# Pedalboard.net
KiCad netlist of a schematic drawn in EAGLE
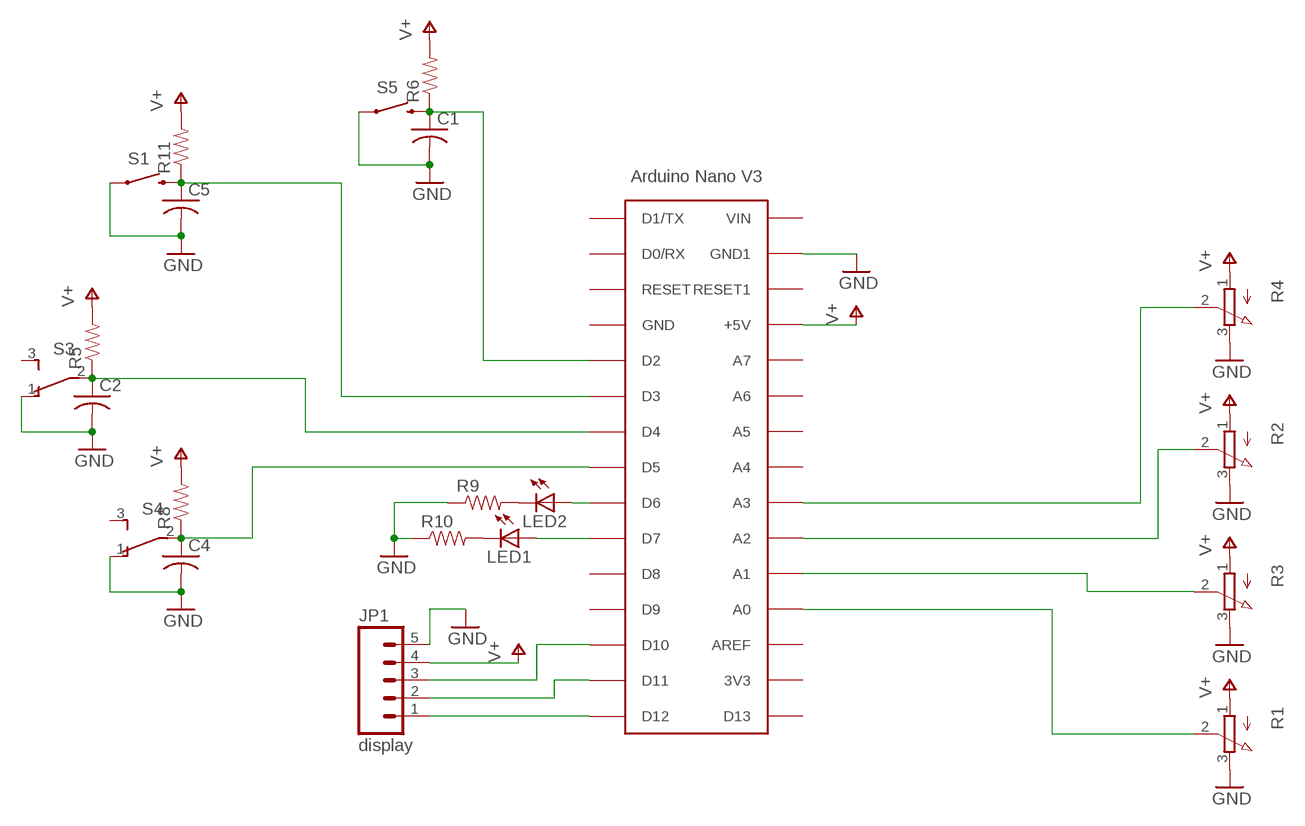
[diagram p0: schematic, sheet 1]

(export (version "E")
  (design (tool "Eeschema 10.0.6"))
  (components
    (comp (ref "C1")
      (value "C-US025-025X050")
      (footprint "eagle-import:C025-025X050")
      (libsource (lib "eagle-import") (part "C-US025-025X050"))
    )
    (comp (ref "C2")
      (value "C-US025-025X050")
      (footprint "eagle-import:C025-025X050")
      (libsource (lib "eagle-import") (part "C-US025-025X050"))
    )
    (comp (ref "C4")
      (value "C-US025-025X050")
      (footprint "eagle-import:C025-025X050")
      (libsource (lib "eagle-import") (part "C-US025-025X050"))
    )
    (comp (ref "C5")
      (value "C-US025-025X050")
      (footprint "eagle-import:C025-025X050")
      (libsource (lib "eagle-import") (part "C-US025-025X050"))
    )
    (comp (ref "JP1")
      (value "display")
      (footprint "eagle-import:1X05")
      (libsource (lib "eagle-import") (part "M05PTH"))
    )
    (comp (ref "LED1")
      (value "LED3MM")
      (footprint "eagle-import:LED3MM")
      (libsource (lib "eagle-import") (part "LED3MM"))
    )
    (comp (ref "LED2")
      (value "LED3MM")
      (footprint "eagle-import:LED3MM")
      (libsource (lib "eagle-import") (part "LED3MM"))
    )
    (comp (ref "R1")
      (value "3RP/1610N")
      (footprint "eagle-import:3RP_1610N")
      (libsource (lib "eagle-import") (part "3RP/1610N"))
    )
    (comp (ref "R2")
      (value "3RP/1610N")
      (footprint "eagle-import:3RP_1610N")
      (libsource (lib "eagle-import") (part "3RP/1610N"))
    )
    (comp (ref "R3")
      (value "3RP/1610N")
      (footprint "eagle-import:3RP_1610N")
      (libsource (lib "eagle-import") (part "3RP/1610N"))
    )
    (comp (ref "R4")
      (value "3RP/1610N")
      (footprint "eagle-import:3RP_1610N")
      (libsource (lib "eagle-import") (part "3RP/1610N"))
    )
    (comp (ref "R5")
      (value "RESISTOREZ")
      (footprint "eagle-import:AXIAL-0.3EZ")
      (libsource (lib "eagle-import") (part "RESISTOREZ"))
    )
    (comp (ref "R6")
      (value "RESISTOREZ")
      (footprint "eagle-import:AXIAL-0.3EZ")
      (libsource (lib "eagle-import") (part "RESISTOREZ"))
    )
    (comp (ref "R8")
      (value "RESISTOREZ")
      (footprint "eagle-import:AXIAL-0.3EZ")
      (libsource (lib "eagle-import") (part "RESISTOREZ"))
    )
    (comp (ref "R9")
      (value "RESISTOREZ")
      (footprint "eagle-import:AXIAL-0.3EZ")
      (libsource (lib "eagle-import") (part "RESISTOREZ"))
    )
    (comp (ref "R10")
      (value "RESISTOREZ")
      (footprint "eagle-import:AXIAL-0.3EZ")
      (libsource (lib "eagle-import") (part "RESISTOREZ"))
    )
    (comp (ref "R11")
      (value "RESISTOREZ")
      (footprint "eagle-import:AXIAL-0.3EZ")
      (libsource (lib "eagle-import") (part "RESISTOREZ"))
    )
    (comp (ref "S1")
      (value "SWITCH-MOMENTARY-2TACTILE-SWITCH-SMD-RIGHT-ANGLE")
      (footprint "eagle-import:TACTILE_SWITCH-SMD-RIGHT-ANGLE")
      (libsource (lib "eagle-import") (part "SWITCH-MOMENTARY-2TACTILE-SWITCH-SMD-RIGHT-ANGLE"))
    )
    (comp (ref "S3")
      (value "TL36PO")
      (footprint "eagle-import:TL3XPO")
      (libsource (lib "eagle-import") (part "TL36PO"))
    )
    (comp (ref "S4")
      (value "TL36PO")
      (footprint "eagle-import:TL3XPO")
      (libsource (lib "eagle-import") (part "TL36PO"))
    )
    (comp (ref "S5")
      (value "SWITCH-MOMENTARY-2TACTILE-SWITCH-SMD-RIGHT-ANGLE")
      (footprint "eagle-import:TACTILE_SWITCH-SMD-RIGHT-ANGLE")
      (libsource (lib "eagle-import") (part "SWITCH-MOMENTARY-2TACTILE-SWITCH-SMD-RIGHT-ANGLE"))
    )
    (comp (ref "U$1")
      (value "ARDUINONANO")
      (footprint "eagle-import:PDIP-32")
      (libsource (lib "eagle-import") (part "ARDUINONANO"))
    )
  )
  (nets
    (net (code "1") (name "GND") (class "Default")
      (node (ref "C1") (pin "2") (pinfunction "2_2") (pintype "passive"))
      (node (ref "C2") (pin "2") (pinfunction "2_2") (pintype "passive"))
      (node (ref "C4") (pin "2") (pinfunction "2_2") (pintype "passive"))
      (node (ref "C5") (pin "2") (pinfunction "2_2") (pintype "passive"))
      (node (ref "JP1") (pin "5") (pinfunction "5_5") (pintype "passive"))
      (node (ref "R1") (pin "3") (pinfunction "E_3") (pintype "passive"))
      (node (ref "R10") (pin "P$1") (pinfunction "1_P$1") (pintype "passive"))
      (node (ref "R2") (pin "3") (pinfunction "E_3") (pintype "passive"))
      (node (ref "R3") (pin "3") (pinfunction "E_3") (pintype "passive"))
      (node (ref "R4") (pin "3") (pinfunction "E_3") (pintype "passive"))
      (node (ref "R9") (pin "P$1") (pinfunction "1_P$1") (pintype "passive"))
      (node (ref "S1") (pin "1") (pinfunction "1_1") (pintype "passive"))
      (node (ref "S3") (pin "1") (pinfunction "O_1") (pintype "passive"))
      (node (ref "S4") (pin "1") (pinfunction "O_1") (pintype "passive"))
      (node (ref "S5") (pin "1") (pinfunction "1_1") (pintype "passive"))
      (node (ref "U$1") (pin "GND1") (pinfunction "GND1_GND1") (pintype "bidirectional"))
    )
    (net (code "2") (name "Net-(JP1-Pad1)") (class "Default")
      (node (ref "JP1") (pin "1") (pinfunction "1_1") (pintype "passive"))
      (node (ref "U$1") (pin "D12") (pinfunction "D12_D12") (pintype "bidirectional"))
    )
    (net (code "3") (name "Net-(JP1-Pad2)") (class "Default")
      (node (ref "JP1") (pin "2") (pinfunction "2_2") (pintype "passive"))
      (node (ref "U$1") (pin "D11") (pinfunction "D11_D11") (pintype "bidirectional"))
    )
    (net (code "4") (name "Net-(JP1-Pad3)") (class "Default")
      (node (ref "JP1") (pin "3") (pinfunction "3_3") (pintype "passive"))
      (node (ref "U$1") (pin "D10") (pinfunction "D10_D10") (pintype "bidirectional"))
    )
    (net (code "5") (name "Net-(LED1-C)") (class "Default")
      (node (ref "LED1") (pin "K") (pinfunction "C_K") (pintype "passive"))
      (node (ref "R10") (pin "P$2") (pinfunction "2_P$2") (pintype "passive"))
    )
    (net (code "6") (name "Net-(LED1-PadA)") (class "Default")
      (node (ref "LED1") (pin "A") (pinfunction "A_A") (pintype "passive"))
      (node (ref "U$1") (pin "D7") (pinfunction "D7_D7") (pintype "bidirectional"))
    )
    (net (code "7") (name "Net-(LED2-C)") (class "Default")
      (node (ref "LED2") (pin "K") (pinfunction "C_K") (pintype "passive"))
      (node (ref "R9") (pin "P$2") (pinfunction "2_P$2") (pintype "passive"))
    )
    (net (code "8") (name "Net-(LED2-PadA)") (class "Default")
      (node (ref "LED2") (pin "A") (pinfunction "A_A") (pintype "passive"))
      (node (ref "U$1") (pin "D6") (pinfunction "D6_D6") (pintype "bidirectional"))
    )
    (net (code "9") (name "Net-(R1-S)") (class "Default")
      (node (ref "R1") (pin "2") (pinfunction "S_2") (pintype "passive"))
      (node (ref "U$1") (pin "A7") (pinfunction "A0_A7") (pintype "bidirectional"))
    )
    (net (code "10") (name "Net-(R2-S)") (class "Default")
      (node (ref "R2") (pin "2") (pinfunction "S_2") (pintype "passive"))
      (node (ref "U$1") (pin "A5") (pinfunction "A2_A5") (pintype "bidirectional"))
    )
    (net (code "11") (name "Net-(R3-S)") (class "Default")
      (node (ref "R3") (pin "2") (pinfunction "S_2") (pintype "passive"))
      (node (ref "U$1") (pin "A6") (pinfunction "A1_A6") (pintype "bidirectional"))
    )
    (net (code "12") (name "Net-(R4-S)") (class "Default")
      (node (ref "R4") (pin "2") (pinfunction "S_2") (pintype "passive"))
      (node (ref "U$1") (pin "A4") (pinfunction "A3_A4") (pintype "bidirectional"))
    )
    (net (code "13") (name "Net-(R5-1)") (class "Default")
      (node (ref "C2") (pin "1") (pinfunction "1_1") (pintype "passive"))
      (node (ref "R5") (pin "P$1") (pinfunction "1_P$1") (pintype "passive"))
      (node (ref "S3") (pin "2") (pinfunction "P_2") (pintype "passive"))
      (node (ref "U$1") (pin "D4") (pinfunction "D4_D4") (pintype "bidirectional"))
    )
    (net (code "14") (name "Net-(R6-1)") (class "Default")
      (node (ref "C1") (pin "1") (pinfunction "1_1") (pintype "passive"))
      (node (ref "R6") (pin "P$1") (pinfunction "1_P$1") (pintype "passive"))
      (node (ref "S5") (pin "2") (pinfunction "2_2") (pintype "passive"))
      (node (ref "U$1") (pin "D2") (pinfunction "D2_D2") (pintype "bidirectional"))
    )
    (net (code "15") (name "Net-(R8-1)") (class "Default")
      (node (ref "C4") (pin "1") (pinfunction "1_1") (pintype "passive"))
      (node (ref "R8") (pin "P$1") (pinfunction "1_P$1") (pintype "passive"))
      (node (ref "S4") (pin "2") (pinfunction "P_2") (pintype "passive"))
      (node (ref "U$1") (pin "D5") (pinfunction "D5_D5") (pintype "bidirectional"))
    )
    (net (code "16") (name "Net-(R11-1)") (class "Default")
      (node (ref "C5") (pin "1") (pinfunction "1_1") (pintype "passive"))
      (node (ref "R11") (pin "P$1") (pinfunction "1_P$1") (pintype "passive"))
      (node (ref "S1") (pin "2") (pinfunction "2_2") (pintype "passive"))
      (node (ref "U$1") (pin "D3") (pinfunction "D3_D3") (pintype "bidirectional"))
    )
    (net (code "17") (name "V+") (class "Default")
      (node (ref "JP1") (pin "4") (pinfunction "4_4") (pintype "passive"))
      (node (ref "R1") (pin "1") (pinfunction "A_1") (pintype "passive"))
      (node (ref "R11") (pin "P$2") (pinfunction "2_P$2") (pintype "passive"))
      (node (ref "R2") (pin "1") (pinfunction "A_1") (pintype "passive"))
      (node (ref "R3") (pin "1") (pinfunction "A_1") (pintype "passive"))
      (node (ref "R4") (pin "1") (pinfunction "A_1") (pintype "passive"))
      (node (ref "R5") (pin "P$2") (pinfunction "2_P$2") (pintype "passive"))
      (node (ref "R6") (pin "P$2") (pinfunction "2_P$2") (pintype "passive"))
      (node (ref "R8") (pin "P$2") (pinfunction "2_P$2") (pintype "passive"))
      (node (ref "U$1") (pin "+5V") (pinfunction "+5V_+5V") (pintype "bidirectional"))
    )
    (net (code "18") (name "unconnected-(S3-S-Pad3)") (class "Default")
      (node (ref "S3") (pin "3") (pinfunction "S_3") (pintype "passive"))
    )
    (net (code "19") (name "unconnected-(S4-S-Pad3)") (class "Default")
      (node (ref "S4") (pin "3") (pinfunction "S_3") (pintype "passive"))
    )
    (net (code "20") (name "unconnected-(U$1-A4-PadA3)") (class "Default")
      (node (ref "U$1") (pin "A3") (pinfunction "A4_A3") (pintype "bidirectional"))
    )
    (net (code "21") (name "unconnected-(U$1-A5-PadA2)") (class "Default")
      (node (ref "U$1") (pin "A2") (pinfunction "A5_A2") (pintype "bidirectional"))
    )
    (net (code "22") (name "unconnected-(U$1-A6-PadA1)") (class "Default")
      (node (ref "U$1") (pin "A1") (pinfunction "A6_A1") (pintype "bidirectional"))
    )
    (net (code "23") (name "unconnected-(U$1-A7-PadA0)") (class "Default")
      (node (ref "U$1") (pin "A0") (pinfunction "A7_A0") (pintype "bidirectional"))
    )
    (net (code "24") (name "unconnected-(U$1-Pad3V3)") (class "Default")
      (node (ref "U$1") (pin "3V3") (pinfunction "3V3_3V3") (pintype "bidirectional"))
    )
    (net (code "25") (name "unconnected-(U$1-PadAREF)") (class "Default")
      (node (ref "U$1") (pin "AREF") (pinfunction "AREF_AREF") (pintype "bidirectional"))
    )
    (net (code "26") (name "unconnected-(U$1-PadD0{slash}RX)") (class "Default")
      (node (ref "U$1") (pin "D0/RX") (pinfunction "D0/RX_D0/RX") (pintype "bidirectional"))
    )
    (net (code "27") (name "unconnected-(U$1-PadD1{slash}TX)") (class "Default")
      (node (ref "U$1") (pin "D1/TX") (pinfunction "D1/TX_D1/TX") (pintype "bidirectional"))
    )
    (net (code "28") (name "unconnected-(U$1-PadD8)") (class "Default")
      (node (ref "U$1") (pin "D8") (pinfunction "D8_D8") (pintype "bidirectional"))
    )
    (net (code "29") (name "unconnected-(U$1-PadD9)") (class "Default")
      (node (ref "U$1") (pin "D9") (pinfunction "D9_D9") (pintype "bidirectional"))
    )
    (net (code "30") (name "unconnected-(U$1-PadD13)") (class "Default")
      (node (ref "U$1") (pin "D13") (pinfunction "D13_D13") (pintype "bidirectional"))
    )
    (net (code "31") (name "unconnected-(U$1-PadGND)") (class "Default")
      (node (ref "U$1") (pin "GND") (pinfunction "GND_GND") (pintype "bidirectional"))
    )
    (net (code "32") (name "unconnected-(U$1-PadRESET)") (class "Default")
      (node (ref "U$1") (pin "RESET") (pinfunction "RESET_RESET") (pintype "bidirectional"))
    )
    (net (code "33") (name "unconnected-(U$1-PadRESET1)") (class "Default")
      (node (ref "U$1") (pin "RESET1") (pinfunction "RESET1_RESET1") (pintype "bidirectional"))
    )
    (net (code "34") (name "unconnected-(U$1-PadVIN)") (class "Default")
      (node (ref "U$1") (pin "VIN") (pinfunction "VIN_VIN") (pintype "bidirectional"))
    )
  )
)
